# FUC.net
KiCad netlist of a schematic drawn in Altium Designer
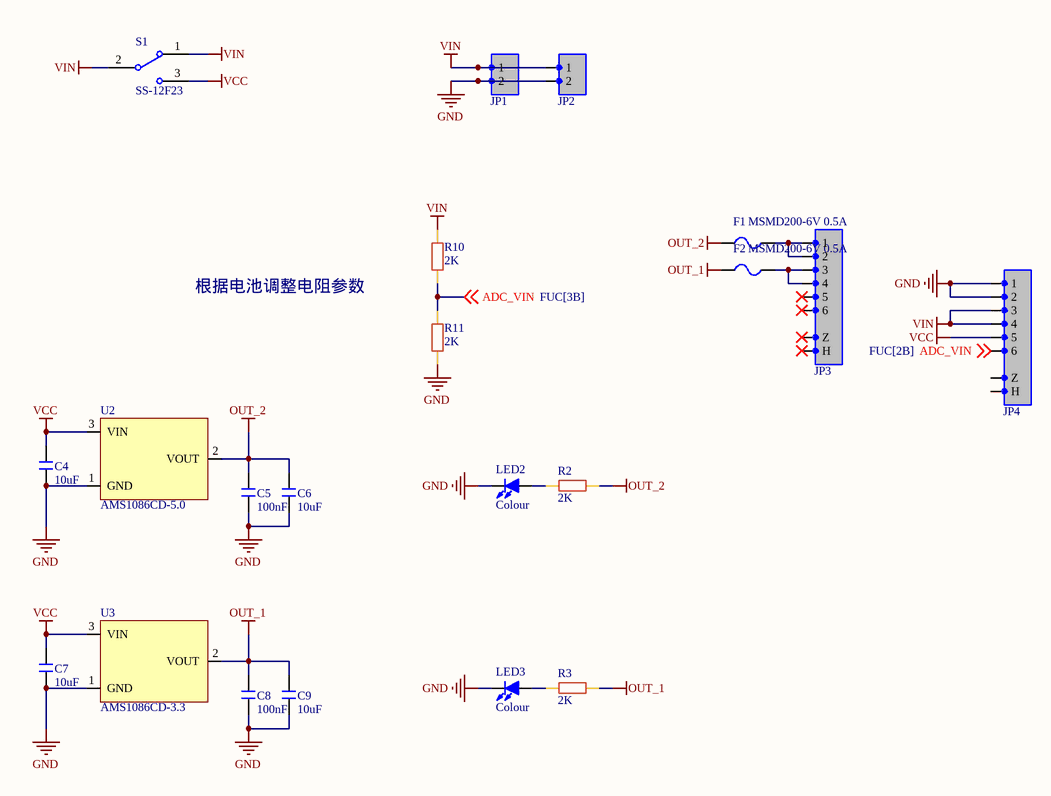
[diagram p0: FUC.SchDoc]

(export (version "E")
  (design (tool "Eeschema 10.0.6"))
  (components
    (comp (ref "C4")
      (value "10uF")
      (footprint "C 0603_L")
      (description "无极性贴片电容")
      (fields (field (name "版权归属") "源创客"))
      (libsource (lib "3.2-电容") (part "C"))
    )
    (comp (ref "C5")
      (value "100nF")
      (footprint "C 0603_L")
      (description "无极性贴片电容")
      (fields (field (name "版权归属") "源创客"))
      (libsource (lib "3.2-电容") (part "C"))
    )
    (comp (ref "C6")
      (value "10uF")
      (footprint "C 0603_L")
      (description "无极性贴片电容")
      (fields (field (name "版权归属") "源创客"))
      (libsource (lib "3.2-电容") (part "C"))
    )
    (comp (ref "C7")
      (value "10uF")
      (footprint "C 0603_L")
      (description "无极性贴片电容")
      (fields (field (name "版权归属") "源创客"))
      (libsource (lib "3.2-电容") (part "C"))
    )
    (comp (ref "C8")
      (value "100nF")
      (footprint "C 0603_L")
      (description "无极性贴片电容")
      (fields (field (name "版权归属") "源创客"))
      (libsource (lib "3.2-电容") (part "C"))
    )
    (comp (ref "C9")
      (value "10uF")
      (footprint "C 0603_L")
      (description "无极性贴片电容")
      (fields (field (name "版权归属") "源创客"))
      (libsource (lib "3.2-电容") (part "C"))
    )
    (comp (ref "F1")
      (value "MSMD200-6V 0.5A")
      (footprint "FU 0805")
      (description "贴片保险丝")
      (fields (field (name "版权归属") "源创客"))
      (libsource (lib "6.3-保险丝") (part "FU"))
    )
    (comp (ref "F2")
      (value "MSMD200-6V 0.5A")
      (footprint "FU 0805")
      (description "贴片保险丝")
      (fields (field (name "版权归属") "源创客"))
      (libsource (lib "6.3-保险丝") (part "FU"))
    )
    (comp (ref "JP1")
      (value "HDR-1X2")
      (footprint "XH2.54-WI-2P")
      (description "2P接插件")
      (fields (field (name "版权归属") "源创客"))
      (libsource (lib "14.6-接插件-脚距2.54") (part "Header 2"))
    )
    (comp (ref "JP2")
      (value "HDR-1X2")
      (footprint "HDR2.54-LI-2P")
      (description "2P接插件")
      (fields (field (name "版权归属") "源创客"))
      (libsource (lib "14.6-接插件-脚距2.54") (part "Header 2"))
    )
    (comp (ref "JP3")
      (value "HDR-1X6")
      (footprint "HDR2.54-LI-6P")
      (description "6P接插件")
      (fields (field (name "版权归属") "源创客"))
      (libsource (lib "14.6-接插件-脚距2.54") (part "Header 6"))
    )
    (comp (ref "JP4")
      (value "HDR-1X6")
      (footprint "HDR2.54-LI-6P")
      (description "6P接插件")
      (fields (field (name "版权归属") "源创客"))
      (libsource (lib "14.6-接插件-脚距2.54") (part "Header 6"))
    )
    (comp (ref "LED2")
      (value "Colour")
      (footprint "LED 0603R")
      (description "贴片LED")
      (fields (field (name "版权归属") "源创客"))
      (libsource (lib "7.1-LED") (part "LED-SMD"))
    )
    (comp (ref "LED3")
      (value "Colour")
      (footprint "LED 0603R")
      (description "贴片LED")
      (fields (field (name "版权归属") "源创客"))
      (libsource (lib "7.1-LED") (part "LED-SMD"))
    )
    (comp (ref "R2")
      (value "2K")
      (footprint "R 0603_L")
      (description "贴片电阻1%精度")
      (libsource (lib "Propitious Clouds_SCHLIB") (part "电阻"))
    )
    (comp (ref "R3")
      (value "2K")
      (footprint "R 0603_L")
      (description "贴片电阻1%精度")
      (libsource (lib "Propitious Clouds_SCHLIB") (part "电阻"))
    )
    (comp (ref "R10")
      (value "2K")
      (footprint "R 0603_L")
      (description "贴片电阻1%精度")
      (libsource (lib "Propitious Clouds_SCHLIB") (part "电阻"))
    )
    (comp (ref "R11")
      (value "2K")
      (footprint "R 0603_L")
      (description "贴片电阻1%精度")
      (libsource (lib "Propitious Clouds_SCHLIB") (part "电阻"))
    )
    (comp (ref "S1")
      (value "SS-12F23")
      (footprint "SS-12D10")
      (description "1路拨动开关")
      (fields (field (name "版权归属") "源创客"))
      (libsource (lib "6.2-开关") (part "SSW-1P"))
    )
    (comp (ref "U2")
      (value "AMS1086CD-5.0")
      (footprint "TO252")
      (libsource (lib "Schlib1") (part "AMS1086CD-5.0"))
    )
    (comp (ref "U3")
      (value "AMS1086CD-3.3")
      (footprint "TO252")
      (libsource (lib "Schlib1") (part "AMS1086CD-5.0"))
    )
  )
  (nets
    (net (code "1") (name "ADC_VIN") (class "Default")
      (node (ref "JP4") (pin "6") (pinfunction "6_6") (pintype "passive"))
      (node (ref "R10") (pin "2") (pinfunction "2_2") (pintype "passive"))
      (node (ref "R11") (pin "1") (pinfunction "1_1") (pintype "passive"))
    )
    (net (code "2") (name "GND") (class "Default")
      (node (ref "C4") (pin "2") (pinfunction "2_2") (pintype "passive"))
      (node (ref "C5") (pin "2") (pinfunction "2_2") (pintype "passive"))
      (node (ref "C6") (pin "2") (pinfunction "2_2") (pintype "passive"))
      (node (ref "C7") (pin "2") (pinfunction "2_2") (pintype "passive"))
      (node (ref "C8") (pin "2") (pinfunction "2_2") (pintype "passive"))
      (node (ref "C9") (pin "2") (pinfunction "2_2") (pintype "passive"))
      (node (ref "JP1") (pin "2") (pinfunction "2_2") (pintype "passive"))
      (node (ref "JP2") (pin "2") (pinfunction "2_2") (pintype "passive"))
      (node (ref "JP4") (pin "1") (pinfunction "1_1") (pintype "passive"))
      (node (ref "JP4") (pin "2") (pinfunction "2_2") (pintype "passive"))
      (node (ref "LED2") (pin "2") (pinfunction "K_2") (pintype "passive"))
      (node (ref "LED3") (pin "2") (pinfunction "K_2") (pintype "passive"))
      (node (ref "R11") (pin "2") (pinfunction "2_2") (pintype "passive"))
      (node (ref "U2") (pin "1") (pinfunction "GND_1") (pintype "passive"))
      (node (ref "U3") (pin "1") (pinfunction "GND_1") (pintype "passive"))
    )
    (net (code "3") (name "Net-(F1-Pad2)") (class "Default")
      (node (ref "F1") (pin "2") (pinfunction "2_2") (pintype "passive"))
      (node (ref "JP3") (pin "1") (pinfunction "1_1") (pintype "passive"))
      (node (ref "JP3") (pin "2") (pinfunction "2_2") (pintype "passive"))
    )
    (net (code "4") (name "Net-(F2-Pad2)") (class "Default")
      (node (ref "F2") (pin "2") (pinfunction "2_2") (pintype "passive"))
      (node (ref "JP3") (pin "3") (pinfunction "3_3") (pintype "passive"))
      (node (ref "JP3") (pin "4") (pinfunction "4_4") (pintype "passive"))
    )
    (net (code "5") (name "Net-(LED2-A)") (class "Default")
      (node (ref "LED2") (pin "1") (pinfunction "A_1") (pintype "passive"))
      (node (ref "R2") (pin "2") (pinfunction "2_2") (pintype "passive"))
    )
    (net (code "6") (name "Net-(LED3-A)") (class "Default")
      (node (ref "LED3") (pin "1") (pinfunction "A_1") (pintype "passive"))
      (node (ref "R3") (pin "2") (pinfunction "2_2") (pintype "passive"))
    )
    (net (code "7") (name "OUT_1") (class "Default")
      (node (ref "C8") (pin "1") (pinfunction "1_1") (pintype "passive"))
      (node (ref "C9") (pin "1") (pinfunction "1_1") (pintype "passive"))
      (node (ref "F2") (pin "1") (pinfunction "1_1") (pintype "passive"))
      (node (ref "R3") (pin "1") (pinfunction "1_1") (pintype "passive"))
      (node (ref "U3") (pin "2") (pinfunction "VOUT_2") (pintype "passive"))
    )
    (net (code "8") (name "OUT_2") (class "Default")
      (node (ref "C5") (pin "1") (pinfunction "1_1") (pintype "passive"))
      (node (ref "C6") (pin "1") (pinfunction "1_1") (pintype "passive"))
      (node (ref "F1") (pin "1") (pinfunction "1_1") (pintype "passive"))
      (node (ref "R2") (pin "1") (pinfunction "1_1") (pintype "passive"))
      (node (ref "U2") (pin "2") (pinfunction "VOUT_2") (pintype "passive"))
    )
    (net (code "9") (name "VCC") (class "Default")
      (node (ref "C4") (pin "1") (pinfunction "1_1") (pintype "passive"))
      (node (ref "C7") (pin "1") (pinfunction "1_1") (pintype "passive"))
      (node (ref "JP4") (pin "5") (pinfunction "5_5") (pintype "passive"))
      (node (ref "S1") (pin "3") (pinfunction "3_3") (pintype "passive"))
      (node (ref "U2") (pin "3") (pinfunction "VIN_3") (pintype "passive"))
      (node (ref "U3") (pin "3") (pinfunction "VIN_3") (pintype "passive"))
    )
    (net (code "10") (name "VIN") (class "Default")
      (node (ref "JP1") (pin "1") (pinfunction "1_1") (pintype "passive"))
      (node (ref "JP2") (pin "1") (pinfunction "1_1") (pintype "passive"))
      (node (ref "JP4") (pin "3") (pinfunction "3_3") (pintype "passive"))
      (node (ref "JP4") (pin "4") (pinfunction "4_4") (pintype "passive"))
      (node (ref "R10") (pin "1") (pinfunction "1_1") (pintype "passive"))
      (node (ref "S1") (pin "1") (pinfunction "1_1") (pintype "passive"))
      (node (ref "S1") (pin "2") (pinfunction "2_2") (pintype "passive"))
    )
    (net (code "11") (name "unconnected-(JP3-H-Pad100)") (class "Default")
      (node (ref "JP3") (pin "100") (pinfunction "H_100") (pintype "passive+no_connect"))
    )
    (net (code "12") (name "unconnected-(JP3-Pad5)") (class "Default")
      (node (ref "JP3") (pin "5") (pinfunction "5_5") (pintype "passive+no_connect"))
    )
    (net (code "13") (name "unconnected-(JP3-Pad6)") (class "Default")
      (node (ref "JP3") (pin "6") (pinfunction "6_6") (pintype "passive+no_connect"))
    )
    (net (code "14") (name "unconnected-(JP3-Z-Pad0)") (class "Default")
      (node (ref "JP3") (pin "0") (pinfunction "Z_0") (pintype "passive+no_connect"))
    )
    (net (code "15") (name "unconnected-(JP4-H-Pad100)") (class "Default")
      (node (ref "JP4") (pin "100") (pinfunction "H_100") (pintype "passive"))
    )
    (net (code "16") (name "unconnected-(JP4-Z-Pad0)") (class "Default")
      (node (ref "JP4") (pin "0") (pinfunction "Z_0") (pintype "passive"))
    )
  )
)
